# Example.net
KiCad netlist of a schematic drawn in EAGLE
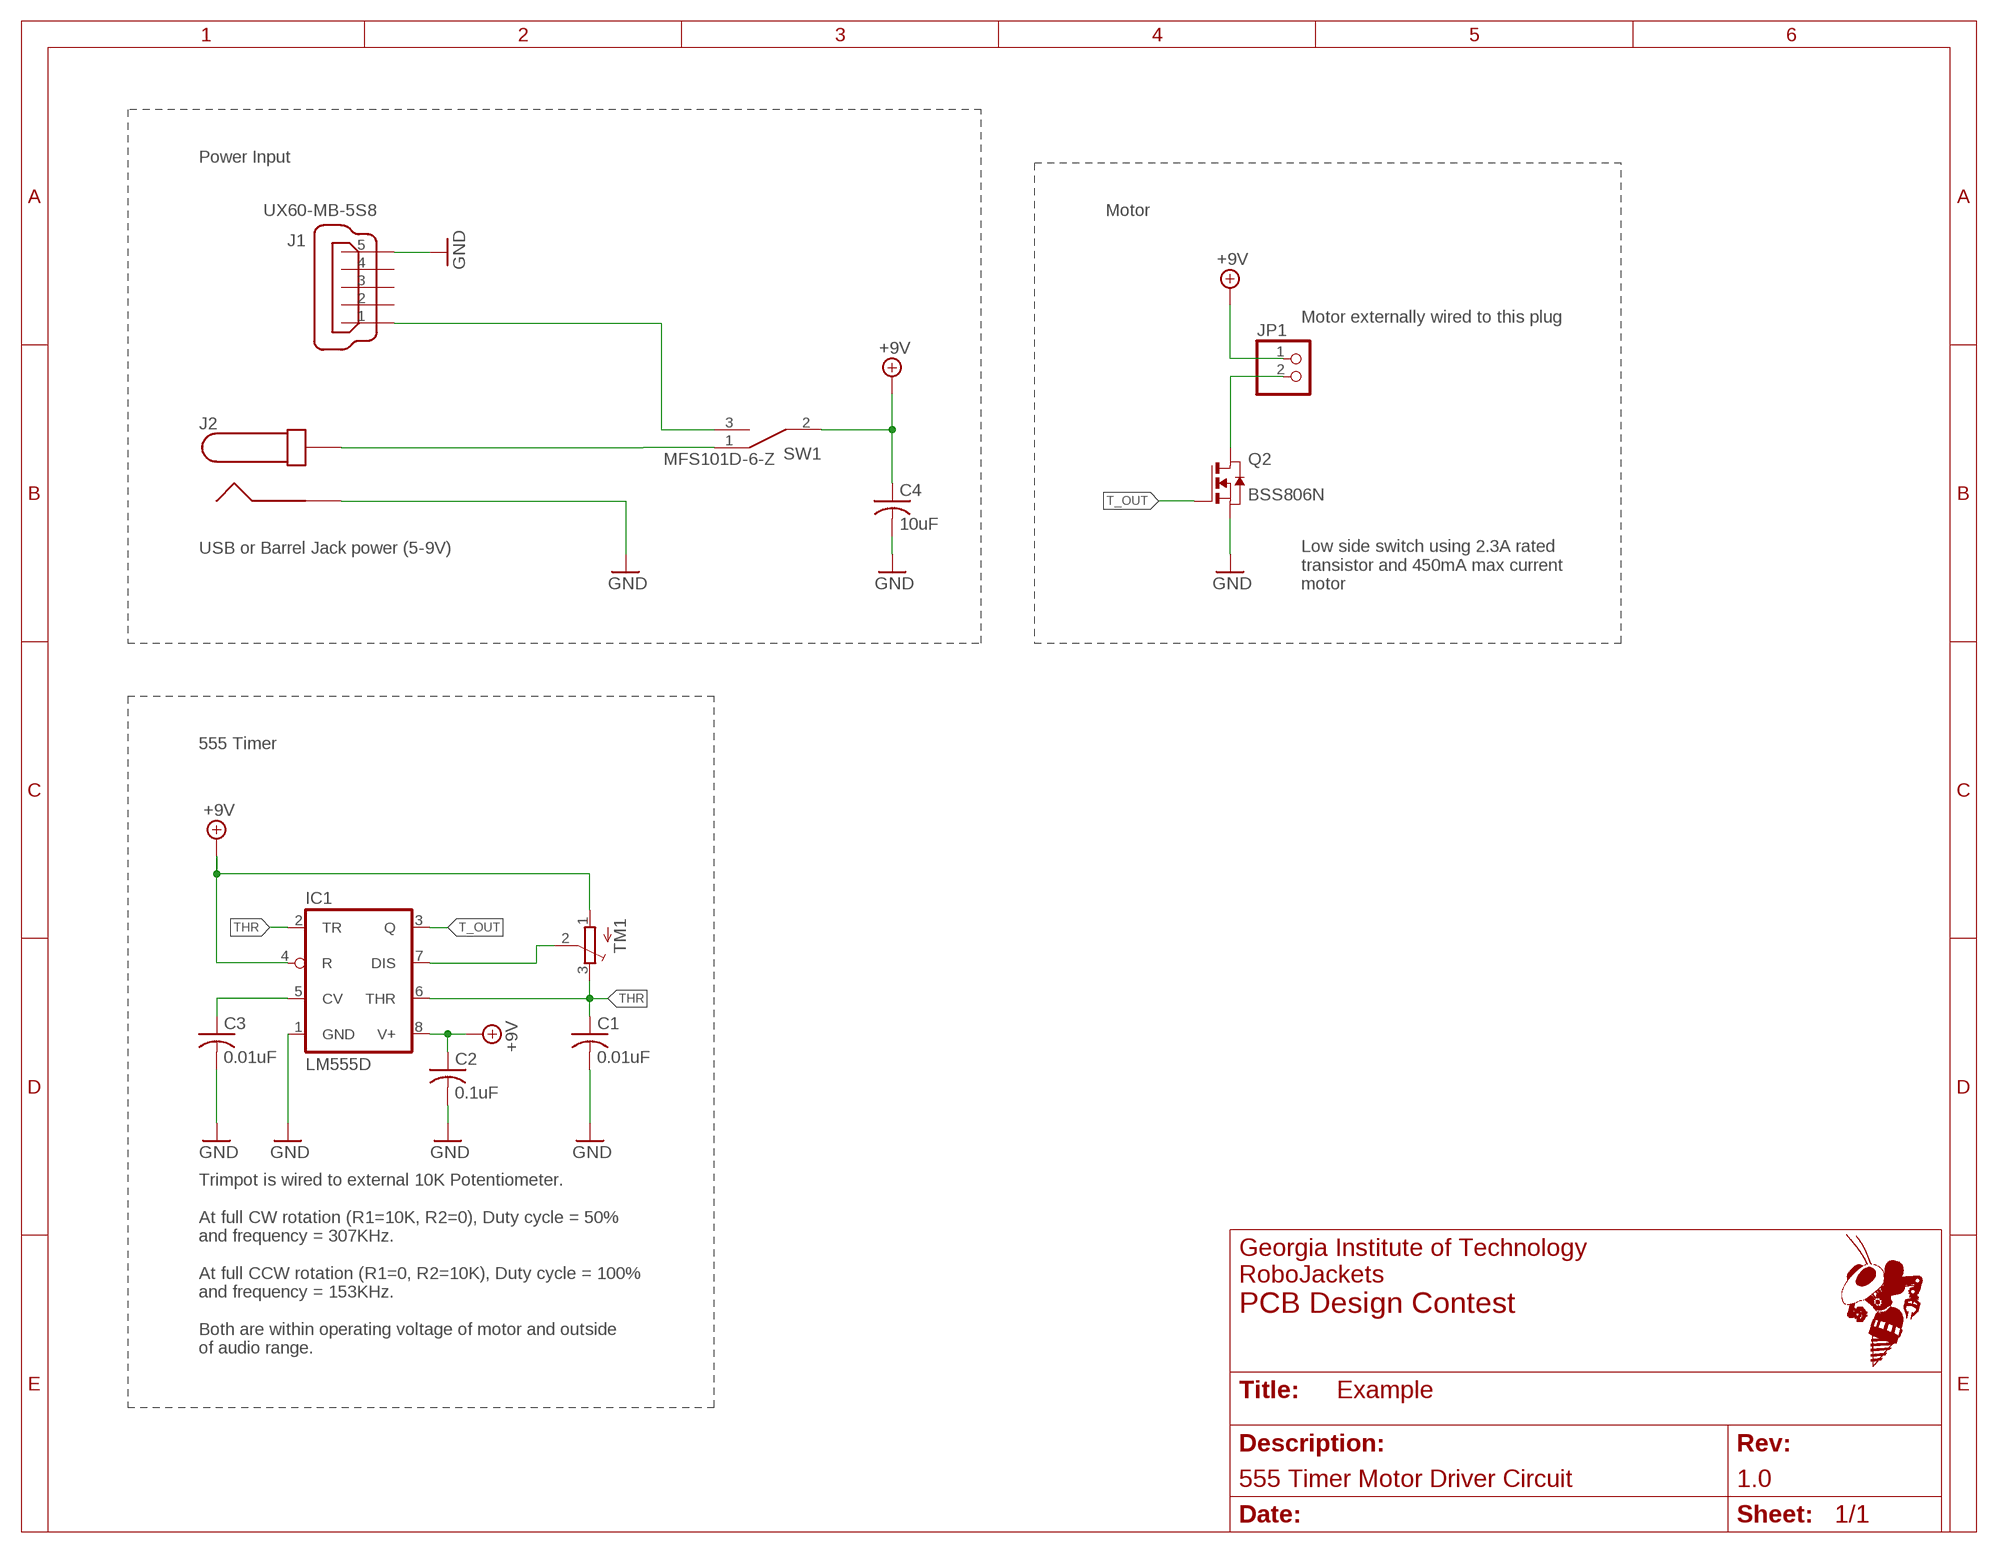
[diagram p0: schematic, sheet 1]

(export (version "E")
  (design (tool "Eeschema 10.0.6"))
  (components
    (comp (ref "C1")
      (value "0.01uF")
      (footprint "eagle-import:C0603")
      (libsource (lib "eagle-import") (part "C-USC0603"))
    )
    (comp (ref "C2")
      (value "0.1uF")
      (footprint "eagle-import:C0603")
      (libsource (lib "eagle-import") (part "C-USC0603"))
    )
    (comp (ref "C3")
      (value "0.01uF")
      (footprint "eagle-import:C0603")
      (libsource (lib "eagle-import") (part "C-USC0603"))
    )
    (comp (ref "C4")
      (value "10uF")
      (footprint "eagle-import:C0603")
      (libsource (lib "eagle-import") (part "C-USC0603"))
    )
    (comp (ref "IC1")
      (value "LM555D")
      (footprint "eagle-import:SO08")
      (libsource (lib "eagle-import") (part "555DLM"))
    )
    (comp (ref "J1")
      (value "UX60-MB-5S8")
      (footprint "eagle-import:UX60-MB-5S8")
      (libsource (lib "eagle-import") (part "UX60-MB-5S?8"))
    )
    (comp (ref "J2")
      (value "PJ-037A")
      (footprint "eagle-import:PJ-037A")
      (libsource (lib "eagle-import") (part "PJ-037A"))
    )
    (comp (ref "JP1")
      (value "PINHD-1X2")
      (footprint "eagle-import:1X02")
      (libsource (lib "eagle-import") (part "PINHD-1X2"))
    )
    (comp (ref "Q2")
      (value "BSS806N")
      (footprint "eagle-import:SOT-23-3")
      (libsource (lib "eagle-import") (part "BSS806N"))
    )
    (comp (ref "SW1")
      (value "MFS101D-6-Z")
      (footprint "eagle-import:MFS101D-6-Z")
      (libsource (lib "eagle-import") (part "MFS101D-6-Z"))
    )
    (comp (ref "TM1")
      (value "TRIMPOT3386")
      (footprint "eagle-import:TRIM-3386")
      (libsource (lib "eagle-import") (part "TRIMPOT3386"))
    )
  )
  (nets
    (net (code "1") (name "+9V") (class "Default")
      (node (ref "C2") (pin "1") (pinfunction "1_1") (pintype "passive"))
      (node (ref "C4") (pin "1") (pinfunction "1_1") (pintype "passive"))
      (node (ref "IC1") (pin "4") (pinfunction "R_4") (pintype "input"))
      (node (ref "IC1") (pin "8") (pinfunction "V+_8") (pintype "power_in"))
      (node (ref "JP1") (pin "1") (pinfunction "1_1") (pintype "passive"))
      (node (ref "SW1") (pin "2") (pinfunction "COMMON_2") (pintype "bidirectional"))
      (node (ref "TM1") (pin "1") (pinfunction "A_1") (pintype "passive"))
    )
    (net (code "2") (name "GND") (class "Default")
      (node (ref "C1") (pin "2") (pinfunction "2_2") (pintype "passive"))
      (node (ref "C2") (pin "2") (pinfunction "2_2") (pintype "passive"))
      (node (ref "C3") (pin "2") (pinfunction "2_2") (pintype "passive"))
      (node (ref "C4") (pin "2") (pinfunction "2_2") (pintype "passive"))
      (node (ref "IC1") (pin "1") (pinfunction "GND_1") (pintype "power_in"))
      (node (ref "J1") (pin "5") (pinfunction "5_5") (pintype "passive"))
      (node (ref "J2") (pin "P$1") (pinfunction "2_P$1") (pintype "bidirectional"))
      (node (ref "Q2") (pin "2") (pinfunction "S_2") (pintype "passive"))
    )
    (net (code "3") (name "Net-(IC1-CV)") (class "Default")
      (node (ref "C3") (pin "1") (pinfunction "1_1") (pintype "passive"))
      (node (ref "IC1") (pin "5") (pinfunction "CV_5") (pintype "input"))
    )
    (net (code "4") (name "Net-(IC1-DIS)") (class "Default")
      (node (ref "IC1") (pin "7") (pinfunction "DIS_7") (pintype "input"))
      (node (ref "TM1") (pin "2") (pinfunction "S_2") (pintype "passive"))
    )
    (net (code "5") (name "Net-(J2-1)") (class "Default")
      (node (ref "J2") (pin "P$2") (pinfunction "1_P$2") (pintype "bidirectional"))
      (node (ref "SW1") (pin "1") (pinfunction "A_1") (pintype "bidirectional"))
    )
    (net (code "6") (name "Net-(Q2-D)") (class "Default")
      (node (ref "JP1") (pin "2") (pinfunction "2_2") (pintype "passive"))
      (node (ref "Q2") (pin "3") (pinfunction "D_3") (pintype "passive"))
    )
    (net (code "7") (name "Net-(SW1-B)") (class "Default")
      (node (ref "J1") (pin "1") (pinfunction "1_1") (pintype "passive"))
      (node (ref "SW1") (pin "3") (pinfunction "B_3") (pintype "bidirectional"))
    )
    (net (code "8") (name "THR") (class "Default")
      (node (ref "C1") (pin "1") (pinfunction "1_1") (pintype "passive"))
      (node (ref "IC1") (pin "2") (pinfunction "TR_2") (pintype "input"))
      (node (ref "IC1") (pin "6") (pinfunction "THR_6") (pintype "input"))
      (node (ref "TM1") (pin "3") (pinfunction "E_3") (pintype "passive"))
    )
    (net (code "9") (name "T_OUT") (class "Default")
      (node (ref "IC1") (pin "3") (pinfunction "Q_3") (pintype "output"))
      (node (ref "Q2") (pin "1") (pinfunction "G_1") (pintype "passive"))
    )
    (net (code "10") (name "unconnected-(J1-Pad2)") (class "Default")
      (node (ref "J1") (pin "2") (pinfunction "2_2") (pintype "passive"))
    )
    (net (code "11") (name "unconnected-(J1-Pad3)") (class "Default")
      (node (ref "J1") (pin "3") (pinfunction "3_3") (pintype "passive"))
    )
    (net (code "12") (name "unconnected-(J1-Pad4)") (class "Default")
      (node (ref "J1") (pin "4") (pinfunction "4_4") (pintype "passive"))
    )
  )
)
